# userver_display.net
KiCad netlist of a schematic drawn in EAGLE
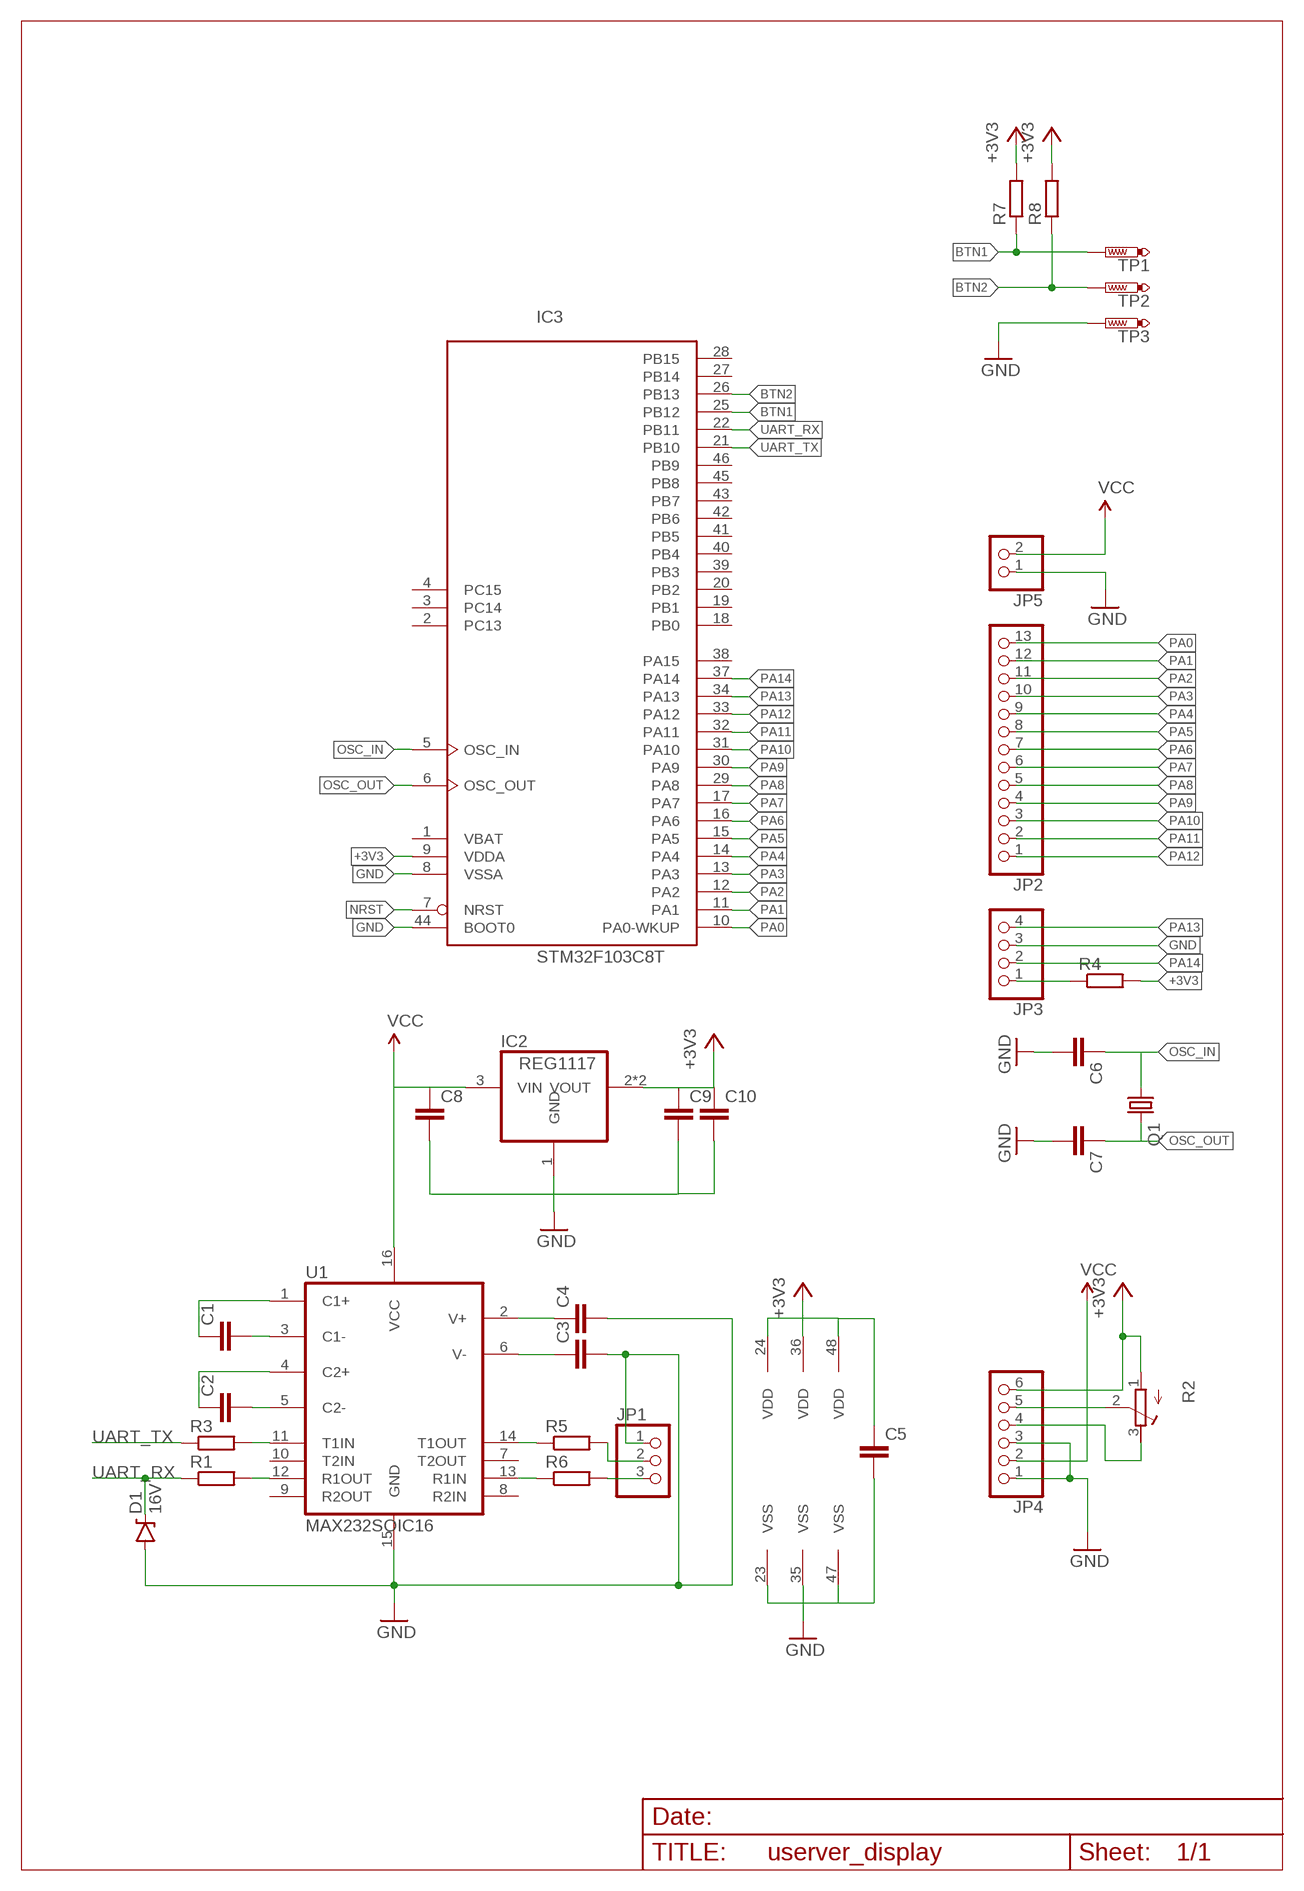
[diagram p0: schematic, sheet 1]

(export (version "E")
  (design (tool "Eeschema 10.0.6"))
  (components
    (comp (ref "C1")
      (value "CC0805")
      (footprint "eagle-import:C0805")
      (libsource (lib "eagle-import") (part "CC0805"))
    )
    (comp (ref "C2")
      (value "CC0805")
      (footprint "eagle-import:C0805")
      (libsource (lib "eagle-import") (part "CC0805"))
    )
    (comp (ref "C3")
      (value "CC0805")
      (footprint "eagle-import:C0805")
      (libsource (lib "eagle-import") (part "CC0805"))
    )
    (comp (ref "C4")
      (value "CC0805")
      (footprint "eagle-import:C0805")
      (libsource (lib "eagle-import") (part "CC0805"))
    )
    (comp (ref "C5")
      (value "CC0805")
      (footprint "eagle-import:C0805")
      (libsource (lib "eagle-import") (part "CC0805"))
    )
    (comp (ref "C6")
      (value "CC0603")
      (footprint "eagle-import:C0603")
      (libsource (lib "eagle-import") (part "CC0603"))
    )
    (comp (ref "C7")
      (value "CC0603")
      (footprint "eagle-import:C0603")
      (libsource (lib "eagle-import") (part "CC0603"))
    )
    (comp (ref "C8")
      (value "CC0805")
      (footprint "eagle-import:C0805")
      (libsource (lib "eagle-import") (part "CC0805"))
    )
    (comp (ref "C9")
      (value "CC0805")
      (footprint "eagle-import:C0805")
      (libsource (lib "eagle-import") (part "CC0805"))
    )
    (comp (ref "C10")
      (value "CC0805")
      (footprint "eagle-import:C0805")
      (libsource (lib "eagle-import") (part "CC0805"))
    )
    (comp (ref "D1")
      (value "16V")
      (footprint "eagle-import:SOD-123")
      (libsource (lib "eagle-import") (part "DIODE-ZENER16V"))
    )
    (comp (ref "IC2")
      (value "REG1117")
      (footprint "eagle-import:SOT223")
      (libsource (lib "eagle-import") (part "REG1117"))
    )
    (comp (ref "IC3")
      (value "STM32F103C8T")
      (footprint "eagle-import:LQFP48")
      (libsource (lib "eagle-import") (part "STM32F103CT8"))
    )
    (comp (ref "JP1")
      (value "PINHD-1X3")
      (footprint "eagle-import:1X03")
      (libsource (lib "eagle-import") (part "PINHD-1X3"))
    )
    (comp (ref "JP2")
      (value "PINHD-1X13")
      (footprint "eagle-import:1X13")
      (libsource (lib "eagle-import") (part "PINHD-1X13"))
    )
    (comp (ref "JP3")
      (value "PINHD-1X4")
      (footprint "eagle-import:1X04")
      (libsource (lib "eagle-import") (part "PINHD-1X4"))
    )
    (comp (ref "JP4")
      (value "PINHD-1X6")
      (footprint "eagle-import:1X06")
      (libsource (lib "eagle-import") (part "PINHD-1X6"))
    )
    (comp (ref "JP5")
      (value "PINHD-1X2")
      (footprint "eagle-import:1X02")
      (libsource (lib "eagle-import") (part "PINHD-1X2"))
    )
    (comp (ref "Q1")
      (value "CRYSTALHC49UP")
      (footprint "eagle-import:HC49UP")
      (libsource (lib "eagle-import") (part "CRYSTALHC49UP"))
    )
    (comp (ref "R1")
      (value "R0603")
      (footprint "eagle-import:0603")
      (libsource (lib "eagle-import") (part "R0603"))
    )
    (comp (ref "R2")
      (value "R-TRIMM64P")
      (footprint "eagle-import:RTRIM64P")
      (libsource (lib "eagle-import") (part "R-TRIMM64P"))
    )
    (comp (ref "R3")
      (value "R0603")
      (footprint "eagle-import:0603")
      (libsource (lib "eagle-import") (part "R0603"))
    )
    (comp (ref "R4")
      (value "R0603")
      (footprint "eagle-import:0603")
      (libsource (lib "eagle-import") (part "R0603"))
    )
    (comp (ref "R5")
      (value "R0603")
      (footprint "eagle-import:0603")
      (libsource (lib "eagle-import") (part "R0603"))
    )
    (comp (ref "R6")
      (value "R0603")
      (footprint "eagle-import:0603")
      (libsource (lib "eagle-import") (part "R0603"))
    )
    (comp (ref "R7")
      (value "R0603")
      (footprint "eagle-import:0603")
      (libsource (lib "eagle-import") (part "R0603"))
    )
    (comp (ref "R8")
      (value "R0603")
      (footprint "eagle-import:0603")
      (libsource (lib "eagle-import") (part "R0603"))
    )
    (comp (ref "TP1")
      (value "PTR1TP10SQ")
      (footprint "eagle-import:TP10SQ")
      (libsource (lib "eagle-import") (part "PTR1TP10SQ"))
    )
    (comp (ref "TP2")
      (value "PTR1TP10SQ")
      (footprint "eagle-import:TP10SQ")
      (libsource (lib "eagle-import") (part "PTR1TP10SQ"))
    )
    (comp (ref "TP3")
      (value "PTR1TP10SQ")
      (footprint "eagle-import:TP10SQ")
      (libsource (lib "eagle-import") (part "PTR1TP10SQ"))
    )
    (comp (ref "U1")
      (value "MAX232SOIC16")
      (footprint "eagle-import:SO016")
      (libsource (lib "eagle-import") (part "MAX232SOIC16"))
    )
  )
  (nets
    (net (code "1") (name "+3V3") (class "Default")
      (node (ref "C10") (pin "1") (pinfunction "1_1") (pintype "passive"))
      (node (ref "C5") (pin "1") (pinfunction "1_1") (pintype "passive"))
      (node (ref "C9") (pin "1") (pinfunction "1_1") (pintype "passive"))
      (node (ref "IC2") (pin "2") (pinfunction "VOUT_2") (pintype "output"))
      (node (ref "IC2") (pin "4") (pinfunction "VOUT_4") (pintype "output"))
      (node (ref "IC3") (pin "24") (pinfunction "VDD_24") (pintype "power_in"))
      (node (ref "IC3") (pin "36") (pinfunction "VDD_36") (pintype "power_in"))
      (node (ref "IC3") (pin "48") (pinfunction "VDD_48") (pintype "power_in"))
      (node (ref "IC3") (pin "9") (pinfunction "VDDA_9") (pintype "power_in"))
      (node (ref "JP4") (pin "6") (pinfunction "6_6") (pintype "passive"))
      (node (ref "R2") (pin "1") (pinfunction "A_1") (pintype "passive"))
      (node (ref "R4") (pin "2") (pinfunction "2_2") (pintype "passive"))
      (node (ref "R7") (pin "2") (pinfunction "2_2") (pintype "passive"))
      (node (ref "R8") (pin "2") (pinfunction "2_2") (pintype "passive"))
    )
    (net (code "2") (name "/VBAT") (class "Default")
      (node (ref "IC3") (pin "1") (pinfunction "VBAT_1") (pintype "power_in"))
    )
    (net (code "3") (name "BTN1") (class "Default")
      (node (ref "IC3") (pin "25") (pinfunction "PB12_25") (pintype "bidirectional"))
      (node (ref "R7") (pin "1") (pinfunction "1_1") (pintype "passive"))
      (node (ref "TP1") (pin "TP") (pinfunction "TP_TP") (pintype "input"))
    )
    (net (code "4") (name "BTN2") (class "Default")
      (node (ref "IC3") (pin "26") (pinfunction "PB13_26") (pintype "bidirectional"))
      (node (ref "R8") (pin "1") (pinfunction "1_1") (pintype "passive"))
      (node (ref "TP2") (pin "TP") (pinfunction "TP_TP") (pintype "input"))
    )
    (net (code "5") (name "GND") (class "Default")
      (node (ref "C10") (pin "2") (pinfunction "2_2") (pintype "passive"))
      (node (ref "C3") (pin "2") (pinfunction "2_2") (pintype "passive"))
      (node (ref "C4") (pin "2") (pinfunction "2_2") (pintype "passive"))
      (node (ref "C5") (pin "2") (pinfunction "2_2") (pintype "passive"))
      (node (ref "C6") (pin "2") (pinfunction "2_2") (pintype "passive"))
      (node (ref "C7") (pin "2") (pinfunction "2_2") (pintype "passive"))
      (node (ref "C8") (pin "2") (pinfunction "2_2") (pintype "passive"))
      (node (ref "C9") (pin "2") (pinfunction "2_2") (pintype "passive"))
      (node (ref "D1") (pin "A") (pinfunction "A_A") (pintype "passive"))
      (node (ref "IC2") (pin "1") (pinfunction "GND_1") (pintype "power_in"))
      (node (ref "IC3") (pin "23") (pinfunction "VSS_23") (pintype "power_in"))
      (node (ref "IC3") (pin "35") (pinfunction "VSS_35") (pintype "power_in"))
      (node (ref "IC3") (pin "44") (pinfunction "BOOT0_44") (pintype "input"))
      (node (ref "IC3") (pin "47") (pinfunction "VSS_47") (pintype "power_in"))
      (node (ref "IC3") (pin "8") (pinfunction "VSSA_8") (pintype "power_in"))
      (node (ref "JP1") (pin "1") (pinfunction "1_1") (pintype "passive"))
      (node (ref "JP3") (pin "3") (pinfunction "3_3") (pintype "passive"))
      (node (ref "JP4") (pin "1") (pinfunction "1_1") (pintype "passive"))
      (node (ref "JP4") (pin "3") (pinfunction "3_3") (pintype "passive"))
      (node (ref "JP5") (pin "1") (pinfunction "1_1") (pintype "passive"))
      (node (ref "TP3") (pin "TP") (pinfunction "TP_TP") (pintype "input"))
      (node (ref "U1") (pin "15") (pinfunction "GND_15") (pintype "bidirectional"))
    )
    (net (code "6") (name "NRST") (class "Default")
      (node (ref "IC3") (pin "7") (pinfunction "NRST_7") (pintype "bidirectional"))
      (node (ref "JP3") (pin "1") (pinfunction "1_1") (pintype "passive"))
      (node (ref "R4") (pin "1") (pinfunction "1_1") (pintype "passive"))
    )
    (net (code "7") (name "Net-(JP1-Pad2)") (class "Default")
      (node (ref "JP1") (pin "2") (pinfunction "2_2") (pintype "passive"))
      (node (ref "R5") (pin "2") (pinfunction "2_2") (pintype "passive"))
    )
    (net (code "8") (name "Net-(JP1-Pad3)") (class "Default")
      (node (ref "JP1") (pin "3") (pinfunction "3_3") (pintype "passive"))
      (node (ref "R6") (pin "2") (pinfunction "2_2") (pintype "passive"))
    )
    (net (code "9") (name "Net-(R2-E)") (class "Default")
      (node (ref "JP4") (pin "4") (pinfunction "4_4") (pintype "passive"))
      (node (ref "R2") (pin "3") (pinfunction "E_3") (pintype "passive"))
    )
    (net (code "10") (name "Net-(R2-S)") (class "Default")
      (node (ref "JP4") (pin "5") (pinfunction "5_5") (pintype "passive"))
      (node (ref "R2") (pin "2") (pinfunction "S_2") (pintype "passive"))
    )
    (net (code "11") (name "Net-(U1-C1+)") (class "Default")
      (node (ref "C1") (pin "1") (pinfunction "1_1") (pintype "passive"))
      (node (ref "U1") (pin "1") (pinfunction "C1+_1") (pintype "bidirectional"))
    )
    (net (code "12") (name "Net-(U1-C1-)") (class "Default")
      (node (ref "C1") (pin "2") (pinfunction "2_2") (pintype "passive"))
      (node (ref "U1") (pin "3") (pinfunction "C1-_3") (pintype "bidirectional"))
    )
    (net (code "13") (name "Net-(U1-C2+)") (class "Default")
      (node (ref "C2") (pin "1") (pinfunction "1_1") (pintype "passive"))
      (node (ref "U1") (pin "4") (pinfunction "C2+_4") (pintype "bidirectional"))
    )
    (net (code "14") (name "Net-(U1-C2-)") (class "Default")
      (node (ref "C2") (pin "2") (pinfunction "2_2") (pintype "passive"))
      (node (ref "U1") (pin "5") (pinfunction "C2-_5") (pintype "bidirectional"))
    )
    (net (code "15") (name "Net-(U1-R1IN)") (class "Default")
      (node (ref "R6") (pin "1") (pinfunction "1_1") (pintype "passive"))
      (node (ref "U1") (pin "13") (pinfunction "R1IN_13") (pintype "input"))
    )
    (net (code "16") (name "Net-(U1-R1OUT)") (class "Default")
      (node (ref "R1") (pin "2") (pinfunction "2_2") (pintype "passive"))
      (node (ref "U1") (pin "12") (pinfunction "R1OUT_12") (pintype "output"))
    )
    (net (code "17") (name "Net-(U1-T1IN)") (class "Default")
      (node (ref "R3") (pin "2") (pinfunction "2_2") (pintype "passive"))
      (node (ref "U1") (pin "11") (pinfunction "T1IN_11") (pintype "input"))
    )
    (net (code "18") (name "Net-(U1-T1OUT)") (class "Default")
      (node (ref "R5") (pin "1") (pinfunction "1_1") (pintype "passive"))
      (node (ref "U1") (pin "14") (pinfunction "T1OUT_14") (pintype "output"))
    )
    (net (code "19") (name "Net-(U1-V+)") (class "Default")
      (node (ref "C4") (pin "1") (pinfunction "1_1") (pintype "passive"))
      (node (ref "U1") (pin "2") (pinfunction "V+_2") (pintype "bidirectional"))
    )
    (net (code "20") (name "Net-(U1-V-)") (class "Default")
      (node (ref "C3") (pin "1") (pinfunction "1_1") (pintype "passive"))
      (node (ref "U1") (pin "6") (pinfunction "V-_6") (pintype "bidirectional"))
    )
    (net (code "21") (name "OSC_IN") (class "Default")
      (node (ref "C6") (pin "1") (pinfunction "1_1") (pintype "passive"))
      (node (ref "IC3") (pin "5") (pinfunction "OSC_IN_5") (pintype "bidirectional"))
      (node (ref "Q1") (pin "1") (pinfunction "1_1") (pintype "passive"))
    )
    (net (code "22") (name "OSC_OUT") (class "Default")
      (node (ref "C7") (pin "1") (pinfunction "1_1") (pintype "passive"))
      (node (ref "IC3") (pin "6") (pinfunction "OSC_OUT_6") (pintype "bidirectional"))
      (node (ref "Q1") (pin "2") (pinfunction "2_2") (pintype "passive"))
    )
    (net (code "23") (name "PA0") (class "Default")
      (node (ref "IC3") (pin "10") (pinfunction "PA0-WKUP_10") (pintype "bidirectional"))
      (node (ref "JP2") (pin "13") (pinfunction "13_13") (pintype "passive"))
    )
    (net (code "24") (name "PA1") (class "Default")
      (node (ref "IC3") (pin "11") (pinfunction "PA1_11") (pintype "bidirectional"))
      (node (ref "JP2") (pin "12") (pinfunction "12_12") (pintype "passive"))
    )
    (net (code "25") (name "PA2") (class "Default")
      (node (ref "IC3") (pin "12") (pinfunction "PA2_12") (pintype "bidirectional"))
      (node (ref "JP2") (pin "11") (pinfunction "11_11") (pintype "passive"))
    )
    (net (code "26") (name "PA3") (class "Default")
      (node (ref "IC3") (pin "13") (pinfunction "PA3_13") (pintype "bidirectional"))
      (node (ref "JP2") (pin "10") (pinfunction "10_10") (pintype "passive"))
    )
    (net (code "27") (name "PA4") (class "Default")
      (node (ref "IC3") (pin "14") (pinfunction "PA4_14") (pintype "bidirectional"))
      (node (ref "JP2") (pin "9") (pinfunction "9_9") (pintype "passive"))
    )
    (net (code "28") (name "PA5") (class "Default")
      (node (ref "IC3") (pin "15") (pinfunction "PA5_15") (pintype "bidirectional"))
      (node (ref "JP2") (pin "8") (pinfunction "8_8") (pintype "passive"))
    )
    (net (code "29") (name "PA6") (class "Default")
      (node (ref "IC3") (pin "16") (pinfunction "PA6_16") (pintype "bidirectional"))
      (node (ref "JP2") (pin "7") (pinfunction "7_7") (pintype "passive"))
    )
    (net (code "30") (name "PA7") (class "Default")
      (node (ref "IC3") (pin "17") (pinfunction "PA7_17") (pintype "bidirectional"))
      (node (ref "JP2") (pin "6") (pinfunction "6_6") (pintype "passive"))
    )
    (net (code "31") (name "PA8") (class "Default")
      (node (ref "IC3") (pin "29") (pinfunction "PA8_29") (pintype "bidirectional"))
      (node (ref "JP2") (pin "5") (pinfunction "5_5") (pintype "passive"))
    )
    (net (code "32") (name "PA9") (class "Default")
      (node (ref "IC3") (pin "30") (pinfunction "PA9_30") (pintype "bidirectional"))
      (node (ref "JP2") (pin "4") (pinfunction "4_4") (pintype "passive"))
    )
    (net (code "33") (name "PA10") (class "Default")
      (node (ref "IC3") (pin "31") (pinfunction "PA10_31") (pintype "bidirectional"))
      (node (ref "JP2") (pin "3") (pinfunction "3_3") (pintype "passive"))
    )
    (net (code "34") (name "PA11") (class "Default")
      (node (ref "IC3") (pin "32") (pinfunction "PA11_32") (pintype "bidirectional"))
      (node (ref "JP2") (pin "2") (pinfunction "2_2") (pintype "passive"))
    )
    (net (code "35") (name "PA12") (class "Default")
      (node (ref "IC3") (pin "33") (pinfunction "PA12_33") (pintype "bidirectional"))
      (node (ref "JP2") (pin "1") (pinfunction "1_1") (pintype "passive"))
    )
    (net (code "36") (name "PA13") (class "Default")
      (node (ref "IC3") (pin "34") (pinfunction "PA13_34") (pintype "bidirectional"))
      (node (ref "JP3") (pin "4") (pinfunction "4_4") (pintype "passive"))
    )
    (net (code "37") (name "PA14") (class "Default")
      (node (ref "IC3") (pin "37") (pinfunction "PA14_37") (pintype "bidirectional"))
      (node (ref "JP3") (pin "2") (pinfunction "2_2") (pintype "passive"))
    )
    (net (code "38") (name "UART_RX") (class "Default")
      (node (ref "D1") (pin "C") (pinfunction "C_C") (pintype "passive"))
      (node (ref "IC3") (pin "22") (pinfunction "PB11_22") (pintype "bidirectional"))
      (node (ref "R1") (pin "1") (pinfunction "1_1") (pintype "passive"))
    )
    (net (code "39") (name "UART_TX") (class "Default")
      (node (ref "IC3") (pin "21") (pinfunction "PB10_21") (pintype "bidirectional"))
      (node (ref "R3") (pin "1") (pinfunction "1_1") (pintype "passive"))
    )
    (net (code "40") (name "VCC") (class "Default")
      (node (ref "C8") (pin "1") (pinfunction "1_1") (pintype "passive"))
      (node (ref "IC2") (pin "3") (pinfunction "VIN_3") (pintype "input"))
      (node (ref "JP4") (pin "2") (pinfunction "2_2") (pintype "passive"))
      (node (ref "JP5") (pin "2") (pinfunction "2_2") (pintype "passive"))
      (node (ref "U1") (pin "16") (pinfunction "VCC_16") (pintype "bidirectional"))
    )
    (net (code "41") (name "unconnected-(IC3A-PA15-Pad38)") (class "Default")
      (node (ref "IC3") (pin "38") (pinfunction "PA15_38") (pintype "bidirectional"))
    )
    (net (code "42") (name "unconnected-(IC3A-PB0-Pad18)") (class "Default")
      (node (ref "IC3") (pin "18") (pinfunction "PB0_18") (pintype "bidirectional"))
    )
    (net (code "43") (name "unconnected-(IC3A-PB1-Pad19)") (class "Default")
      (node (ref "IC3") (pin "19") (pinfunction "PB1_19") (pintype "bidirectional"))
    )
    (net (code "44") (name "unconnected-(IC3A-PB2-Pad20)") (class "Default")
      (node (ref "IC3") (pin "20") (pinfunction "PB2_20") (pintype "bidirectional"))
    )
    (net (code "45") (name "unconnected-(IC3A-PB3-Pad39)") (class "Default")
      (node (ref "IC3") (pin "39") (pinfunction "PB3_39") (pintype "bidirectional"))
    )
    (net (code "46") (name "unconnected-(IC3A-PB4-Pad40)") (class "Default")
      (node (ref "IC3") (pin "40") (pinfunction "PB4_40") (pintype "bidirectional"))
    )
    (net (code "47") (name "unconnected-(IC3A-PB5-Pad41)") (class "Default")
      (node (ref "IC3") (pin "41") (pinfunction "PB5_41") (pintype "bidirectional"))
    )
    (net (code "48") (name "unconnected-(IC3A-PB6-Pad42)") (class "Default")
      (node (ref "IC3") (pin "42") (pinfunction "PB6_42") (pintype "bidirectional"))
    )
    (net (code "49") (name "unconnected-(IC3A-PB7-Pad43)") (class "Default")
      (node (ref "IC3") (pin "43") (pinfunction "PB7_43") (pintype "bidirectional"))
    )
    (net (code "50") (name "unconnected-(IC3A-PB8-Pad45)") (class "Default")
      (node (ref "IC3") (pin "45") (pinfunction "PB8_45") (pintype "bidirectional"))
    )
    (net (code "51") (name "unconnected-(IC3A-PB9-Pad46)") (class "Default")
      (node (ref "IC3") (pin "46") (pinfunction "PB9_46") (pintype "bidirectional"))
    )
    (net (code "52") (name "unconnected-(IC3A-PB14-Pad27)") (class "Default")
      (node (ref "IC3") (pin "27") (pinfunction "PB14_27") (pintype "bidirectional"))
    )
    (net (code "53") (name "unconnected-(IC3A-PB15-Pad28)") (class "Default")
      (node (ref "IC3") (pin "28") (pinfunction "PB15_28") (pintype "bidirectional"))
    )
    (net (code "54") (name "unconnected-(IC3A-PC13-Pad2)") (class "Default")
      (node (ref "IC3") (pin "2") (pinfunction "PC13_2") (pintype "bidirectional"))
    )
    (net (code "55") (name "unconnected-(IC3A-PC14-Pad3)") (class "Default")
      (node (ref "IC3") (pin "3") (pinfunction "PC14_3") (pintype "bidirectional"))
    )
    (net (code "56") (name "unconnected-(IC3A-PC15-Pad4)") (class "Default")
      (node (ref "IC3") (pin "4") (pinfunction "PC15_4") (pintype "bidirectional"))
    )
    (net (code "57") (name "unconnected-(U1-R2IN-Pad8)") (class "Default")
      (node (ref "U1") (pin "8") (pinfunction "R2IN_8") (pintype "input"))
    )
    (net (code "58") (name "unconnected-(U1-R2OUT-Pad9)") (class "Default")
      (node (ref "U1") (pin "9") (pinfunction "R2OUT_9") (pintype "output"))
    )
    (net (code "59") (name "unconnected-(U1-T2IN-Pad10)") (class "Default")
      (node (ref "U1") (pin "10") (pinfunction "T2IN_10") (pintype "input"))
    )
    (net (code "60") (name "unconnected-(U1-T2OUT-Pad7)") (class "Default")
      (node (ref "U1") (pin "7") (pinfunction "T2OUT_7") (pintype "output"))
    )
  )
)
